# fastkey_-_v2.net
KiCad netlist of a schematic drawn in EAGLE
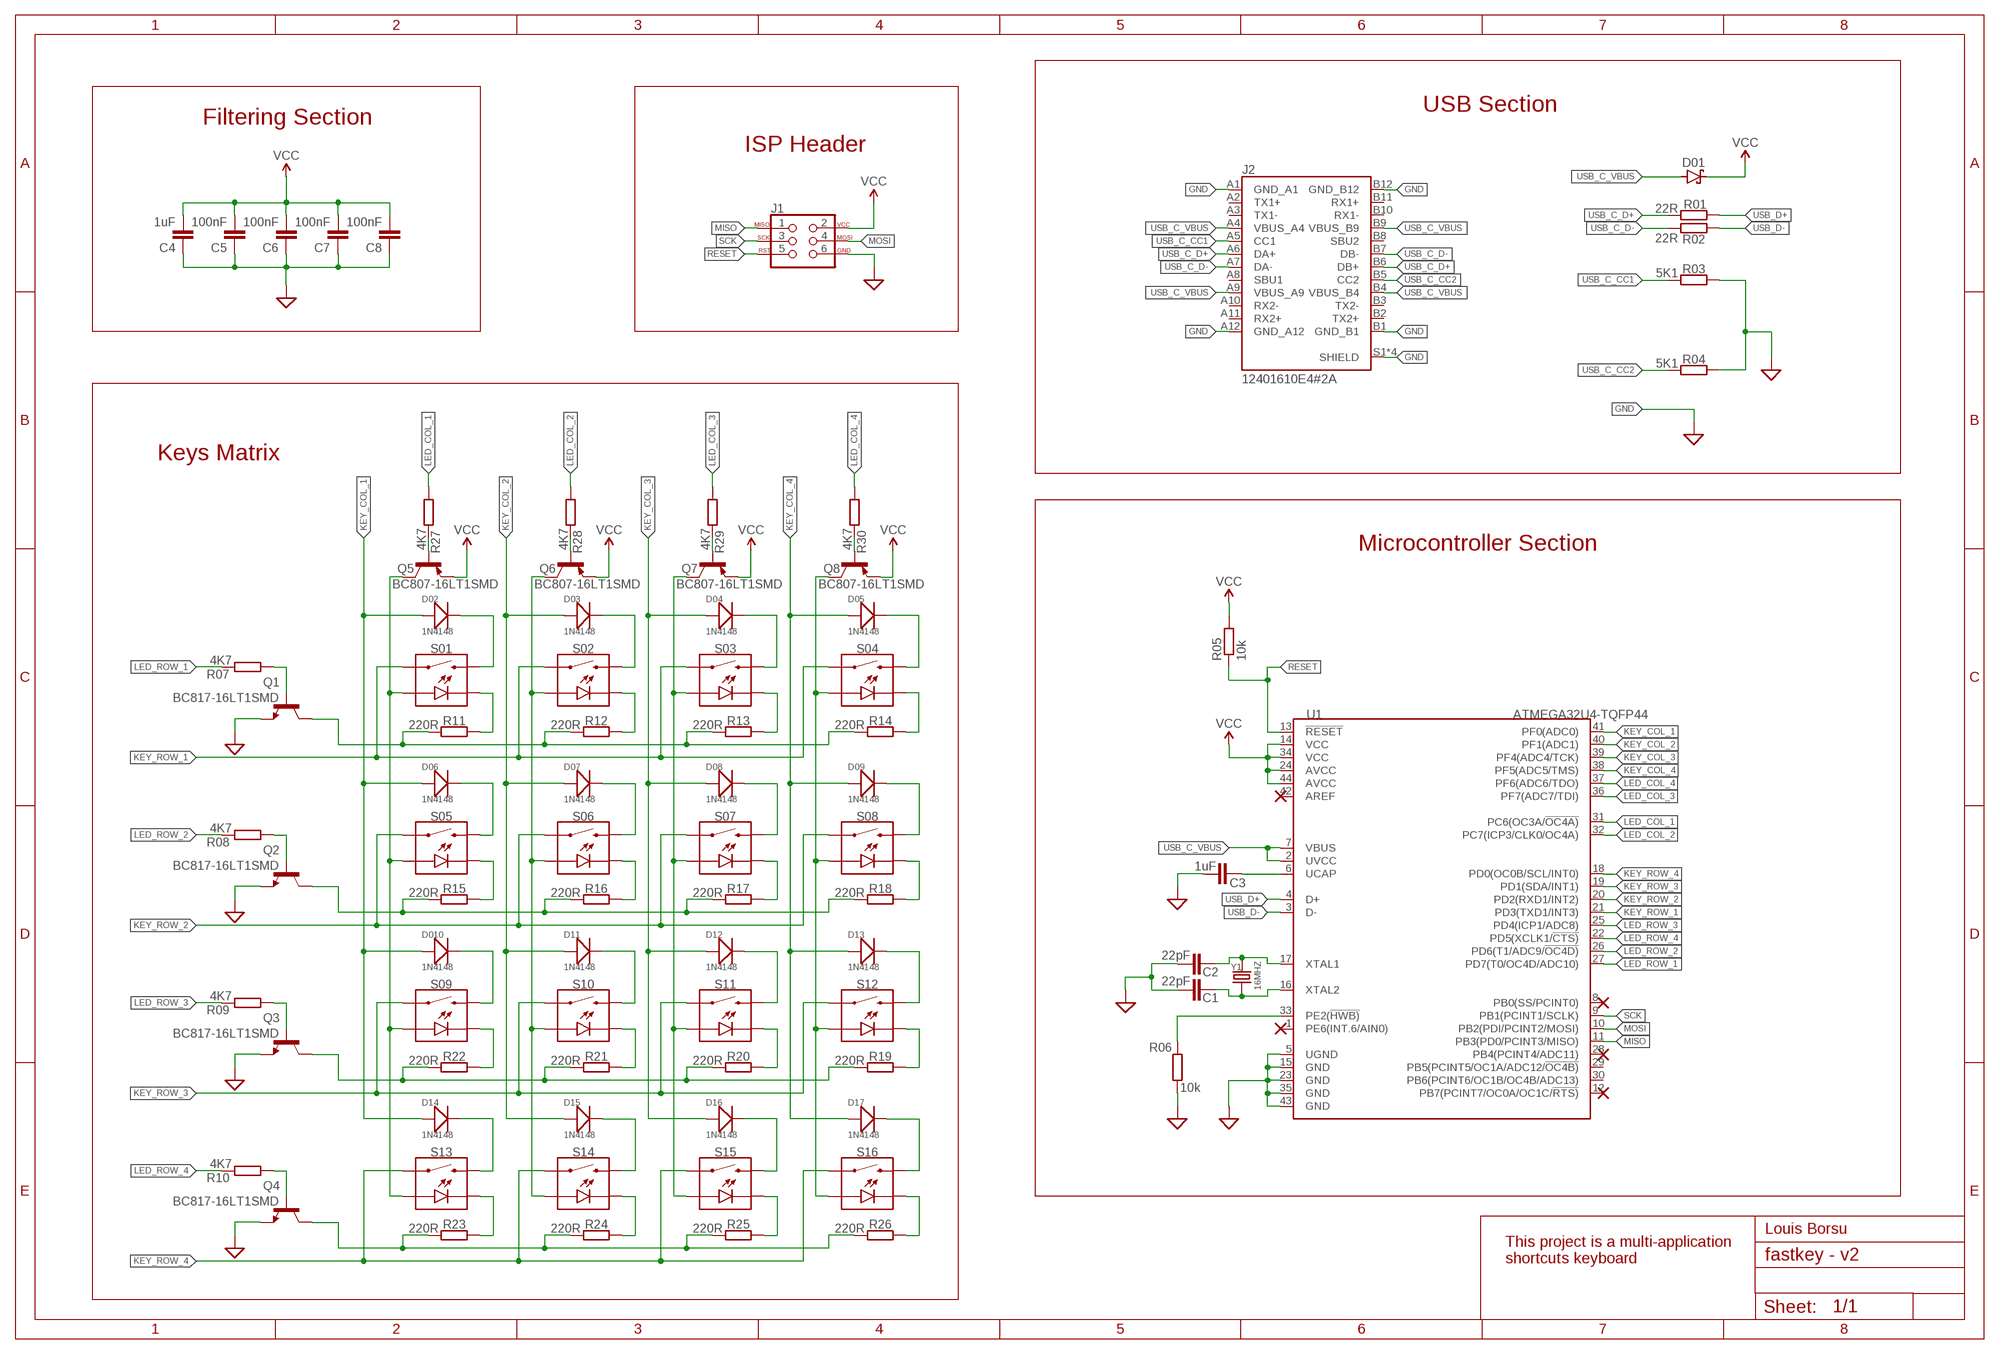
[diagram p0: schematic, sheet 1]

(export (version "E")
  (design (tool "Eeschema 10.0.6"))
  (components
    (comp (ref "C1")
      (value "22pF")
      (footprint "eagle-import:RESC0805_M")
      (fields (field (name "SPICEPREFIX") "C"))
      (libsource (lib "eagle-import") (part "CAPACITOR_0805_M"))
    )
    (comp (ref "C2")
      (value "22pF")
      (footprint "eagle-import:RESC0805_M")
      (fields (field (name "SPICEPREFIX") "C"))
      (libsource (lib "eagle-import") (part "CAPACITOR_0805_M"))
    )
    (comp (ref "C3")
      (value "1uF")
      (footprint "eagle-import:RESC0805_M")
      (fields (field (name "SPICEPREFIX") "C"))
      (libsource (lib "eagle-import") (part "CAPACITOR_0805_M"))
    )
    (comp (ref "C4")
      (value "1uF")
      (footprint "eagle-import:RESC0805_M")
      (fields (field (name "SPICEPREFIX") "C"))
      (libsource (lib "eagle-import") (part "CAPACITOR_0805_M"))
    )
    (comp (ref "C5")
      (value "100nF")
      (footprint "eagle-import:RESC0805_M")
      (fields (field (name "SPICEPREFIX") "C"))
      (libsource (lib "eagle-import") (part "CAPACITOR_0805_M"))
    )
    (comp (ref "C6")
      (value "100nF")
      (footprint "eagle-import:RESC0805_M")
      (libsource (lib "eagle-import") (part "CAPACITOR_0805_M"))
    )
    (comp (ref "C7")
      (value "100nF")
      (footprint "eagle-import:RESC0805_M")
      (fields (field (name "SPICEPREFIX") "C"))
      (libsource (lib "eagle-import") (part "CAPACITOR_0805_M"))
    )
    (comp (ref "C8")
      (value "100nF")
      (footprint "eagle-import:RESC0805_M")
      (fields (field (name "SPICEPREFIX") "C"))
      (libsource (lib "eagle-import") (part "CAPACITOR_0805_M"))
    )
    (comp (ref "D01")
      (value "SCHOTTKY-DIODESMD")
      (footprint "eagle-import:SMB")
      (libsource (lib "eagle-import") (part "SCHOTTKY-DIODESMD"))
    )
    (comp (ref "D02")
      (value "1N4148")
      (footprint "eagle-import:LL-34")
      (libsource (lib "eagle-import") (part "SMD-DIODE-SWITCH-1N4148(LL-34)"))
    )
    (comp (ref "D03")
      (value "1N4148")
      (footprint "eagle-import:LL-34")
      (libsource (lib "eagle-import") (part "SMD-DIODE-SWITCH-1N4148(LL-34)"))
    )
    (comp (ref "D04")
      (value "1N4148")
      (footprint "eagle-import:LL-34")
      (libsource (lib "eagle-import") (part "SMD-DIODE-SWITCH-1N4148(LL-34)"))
    )
    (comp (ref "D05")
      (value "1N4148")
      (footprint "eagle-import:LL-34")
      (libsource (lib "eagle-import") (part "SMD-DIODE-SWITCH-1N4148(LL-34)"))
    )
    (comp (ref "D06")
      (value "1N4148")
      (footprint "eagle-import:LL-34")
      (libsource (lib "eagle-import") (part "SMD-DIODE-SWITCH-1N4148(LL-34)"))
    )
    (comp (ref "D07")
      (value "1N4148")
      (footprint "eagle-import:LL-34")
      (libsource (lib "eagle-import") (part "SMD-DIODE-SWITCH-1N4148(LL-34)"))
    )
    (comp (ref "D08")
      (value "1N4148")
      (footprint "eagle-import:LL-34")
      (libsource (lib "eagle-import") (part "SMD-DIODE-SWITCH-1N4148(LL-34)"))
    )
    (comp (ref "D09")
      (value "1N4148")
      (footprint "eagle-import:LL-34")
      (libsource (lib "eagle-import") (part "SMD-DIODE-SWITCH-1N4148(LL-34)"))
    )
    (comp (ref "D010")
      (value "1N4148")
      (footprint "eagle-import:LL-34")
      (libsource (lib "eagle-import") (part "SMD-DIODE-SWITCH-1N4148(LL-34)"))
    )
    (comp (ref "D11")
      (value "1N4148")
      (footprint "eagle-import:LL-34")
      (libsource (lib "eagle-import") (part "SMD-DIODE-SWITCH-1N4148(LL-34)"))
    )
    (comp (ref "D12")
      (value "1N4148")
      (footprint "eagle-import:LL-34")
      (libsource (lib "eagle-import") (part "SMD-DIODE-SWITCH-1N4148(LL-34)"))
    )
    (comp (ref "D13")
      (value "1N4148")
      (footprint "eagle-import:LL-34")
      (libsource (lib "eagle-import") (part "SMD-DIODE-SWITCH-1N4148(LL-34)"))
    )
    (comp (ref "D14")
      (value "1N4148")
      (footprint "eagle-import:LL-34")
      (libsource (lib "eagle-import") (part "SMD-DIODE-SWITCH-1N4148(LL-34)"))
    )
    (comp (ref "D15")
      (value "1N4148")
      (footprint "eagle-import:LL-34")
      (libsource (lib "eagle-import") (part "SMD-DIODE-SWITCH-1N4148(LL-34)"))
    )
    (comp (ref "D16")
      (value "1N4148")
      (footprint "eagle-import:LL-34")
      (libsource (lib "eagle-import") (part "SMD-DIODE-SWITCH-1N4148(LL-34)"))
    )
    (comp (ref "D17")
      (value "1N4148")
      (footprint "eagle-import:LL-34")
      (libsource (lib "eagle-import") (part "SMD-DIODE-SWITCH-1N4148(LL-34)"))
    )
    (comp (ref "J1")
      (value "AVR_SPI_PROG_3X22X3_LOCK")
      (footprint "eagle-import:2X3_LOCK")
      (libsource (lib "eagle-import") (part "AVR_SPI_PROG_3X22X3_LOCK"))
    )
    (comp (ref "J2")
      (value "12401610E4#2A")
      (footprint "eagle-import:AMPHENOL_12401610E4#2A")
      (fields (field (name "DIGI-KEY_PART_NUMBER") "12401610E4#2ACT-ND") (field (name "MF") "Amphenol ICC"))
      (libsource (lib "eagle-import") (part "12401610E4#2A"))
    )
    (comp (ref "Q1")
      (value "BC817-16LT1SMD")
      (footprint "eagle-import:SOT23-BEC")
      (libsource (lib "eagle-import") (part "BC817SMD-16LT1"))
    )
    (comp (ref "Q2")
      (value "BC817-16LT1SMD")
      (footprint "eagle-import:SOT23-BEC")
      (libsource (lib "eagle-import") (part "BC817SMD-16LT1"))
    )
    (comp (ref "Q3")
      (value "BC817-16LT1SMD")
      (footprint "eagle-import:SOT23-BEC")
      (libsource (lib "eagle-import") (part "BC817SMD-16LT1"))
    )
    (comp (ref "Q4")
      (value "BC817-16LT1SMD")
      (footprint "eagle-import:SOT23-BEC")
      (libsource (lib "eagle-import") (part "BC817SMD-16LT1"))
    )
    (comp (ref "Q5")
      (value "BC807-16LT1SMD")
      (footprint "eagle-import:SOT23-BEC")
      (libsource (lib "eagle-import") (part "BC807SMD-16LT1"))
    )
    (comp (ref "Q6")
      (value "BC807-16LT1SMD")
      (footprint "eagle-import:SOT23-BEC")
      (libsource (lib "eagle-import") (part "BC807SMD-16LT1"))
    )
    (comp (ref "Q7")
      (value "BC807-16LT1SMD")
      (footprint "eagle-import:SOT23-BEC")
      (libsource (lib "eagle-import") (part "BC807SMD-16LT1"))
    )
    (comp (ref "Q8")
      (value "BC807-16LT1SMD")
      (footprint "eagle-import:SOT23-BEC")
      (libsource (lib "eagle-import") (part "BC807SMD-16LT1"))
    )
    (comp (ref "R01")
      (value "22R")
      (footprint "eagle-import:R0805")
      (libsource (lib "eagle-import") (part "R-EU_R0805"))
    )
    (comp (ref "R02")
      (value "22R")
      (footprint "eagle-import:R0805")
      (libsource (lib "eagle-import") (part "R-EU_R0805"))
    )
    (comp (ref "R03")
      (value "5K1")
      (footprint "eagle-import:R0805")
      (libsource (lib "eagle-import") (part "R-EU_R0805"))
    )
    (comp (ref "R04")
      (value "5K1")
      (footprint "eagle-import:R0805")
      (libsource (lib "eagle-import") (part "R-EU_R0805"))
    )
    (comp (ref "R05")
      (value "10k")
      (footprint "eagle-import:R0805")
      (libsource (lib "eagle-import") (part "R-EU_R0805"))
    )
    (comp (ref "R06")
      (value "10k")
      (footprint "eagle-import:R0805")
      (libsource (lib "eagle-import") (part "R-EU_R0805"))
    )
    (comp (ref "R07")
      (value "4K7")
      (footprint "eagle-import:R0805")
      (libsource (lib "eagle-import") (part "R-EU_R0805"))
    )
    (comp (ref "R08")
      (value "4K7")
      (footprint "eagle-import:R0805")
      (libsource (lib "eagle-import") (part "R-EU_R0805"))
    )
    (comp (ref "R09")
      (value "4K7")
      (footprint "eagle-import:R0805")
      (libsource (lib "eagle-import") (part "R-EU_R0805"))
    )
    (comp (ref "R10")
      (value "4K7")
      (footprint "eagle-import:R0805")
      (libsource (lib "eagle-import") (part "R-EU_R0805"))
    )
    (comp (ref "R11")
      (value "220R")
      (footprint "eagle-import:R0805")
      (libsource (lib "eagle-import") (part "R-EU_R0805"))
    )
    (comp (ref "R12")
      (value "220R")
      (footprint "eagle-import:R0805")
      (libsource (lib "eagle-import") (part "R-EU_R0805"))
    )
    (comp (ref "R13")
      (value "220R")
      (footprint "eagle-import:R0805")
      (libsource (lib "eagle-import") (part "R-EU_R0805"))
    )
    (comp (ref "R14")
      (value "220R")
      (footprint "eagle-import:R0805")
      (libsource (lib "eagle-import") (part "R-EU_R0805"))
    )
    (comp (ref "R15")
      (value "220R")
      (footprint "eagle-import:R0805")
      (libsource (lib "eagle-import") (part "R-EU_R0805"))
    )
    (comp (ref "R16")
      (value "220R")
      (footprint "eagle-import:R0805")
      (libsource (lib "eagle-import") (part "R-EU_R0805"))
    )
    (comp (ref "R17")
      (value "220R")
      (footprint "eagle-import:R0805")
      (libsource (lib "eagle-import") (part "R-EU_R0805"))
    )
    (comp (ref "R18")
      (value "220R")
      (footprint "eagle-import:R0805")
      (libsource (lib "eagle-import") (part "R-EU_R0805"))
    )
    (comp (ref "R19")
      (value "220R")
      (footprint "eagle-import:R0805")
      (libsource (lib "eagle-import") (part "R-EU_R0805"))
    )
    (comp (ref "R20")
      (value "220R")
      (footprint "eagle-import:R0805")
      (libsource (lib "eagle-import") (part "R-EU_R0805"))
    )
    (comp (ref "R21")
      (value "220R")
      (footprint "eagle-import:R0805")
      (libsource (lib "eagle-import") (part "R-EU_R0805"))
    )
    (comp (ref "R22")
      (value "220R")
      (footprint "eagle-import:R0805")
      (libsource (lib "eagle-import") (part "R-EU_R0805"))
    )
    (comp (ref "R23")
      (value "220R")
      (footprint "eagle-import:R0805")
      (libsource (lib "eagle-import") (part "R-EU_R0805"))
    )
    (comp (ref "R24")
      (value "220R")
      (footprint "eagle-import:R0805")
      (libsource (lib "eagle-import") (part "R-EU_R0805"))
    )
    (comp (ref "R25")
      (value "220R")
      (footprint "eagle-import:R0805")
      (libsource (lib "eagle-import") (part "R-EU_R0805"))
    )
    (comp (ref "R26")
      (value "220R")
      (footprint "eagle-import:R0805")
      (libsource (lib "eagle-import") (part "R-EU_R0805"))
    )
    (comp (ref "R27")
      (value "4K7")
      (footprint "eagle-import:R0805")
      (libsource (lib "eagle-import") (part "R-EU_R0805"))
    )
    (comp (ref "R28")
      (value "4K7")
      (footprint "eagle-import:R0805")
      (libsource (lib "eagle-import") (part "R-EU_R0805"))
    )
    (comp (ref "R29")
      (value "4K7")
      (footprint "eagle-import:R0805")
      (libsource (lib "eagle-import") (part "R-EU_R0805"))
    )
    (comp (ref "R30")
      (value "4K7")
      (footprint "eagle-import:R0805")
      (libsource (lib "eagle-import") (part "R-EU_R0805"))
    )
    (comp (ref "S01")
      (value "MOMENTARY-SWITCH-SPST-LED-PTH-CHERRY")
      (footprint "eagle-import:CHERRY-MX-LED")
      (libsource (lib "eagle-import") (part "MOMENTARY-SWITCH-SPST-LED-PTH-CHERRY"))
    )
    (comp (ref "S02")
      (value "MOMENTARY-SWITCH-SPST-LED-PTH-CHERRY")
      (footprint "eagle-import:CHERRY-MX-LED")
      (libsource (lib "eagle-import") (part "MOMENTARY-SWITCH-SPST-LED-PTH-CHERRY"))
    )
    (comp (ref "S03")
      (value "MOMENTARY-SWITCH-SPST-LED-PTH-CHERRY")
      (footprint "eagle-import:CHERRY-MX-LED")
      (libsource (lib "eagle-import") (part "MOMENTARY-SWITCH-SPST-LED-PTH-CHERRY"))
    )
    (comp (ref "S04")
      (value "MOMENTARY-SWITCH-SPST-LED-PTH-CHERRY")
      (footprint "eagle-import:CHERRY-MX-LED")
      (libsource (lib "eagle-import") (part "MOMENTARY-SWITCH-SPST-LED-PTH-CHERRY"))
    )
    (comp (ref "S05")
      (value "MOMENTARY-SWITCH-SPST-LED-PTH-CHERRY")
      (footprint "eagle-import:CHERRY-MX-LED")
      (libsource (lib "eagle-import") (part "MOMENTARY-SWITCH-SPST-LED-PTH-CHERRY"))
    )
    (comp (ref "S06")
      (value "MOMENTARY-SWITCH-SPST-LED-PTH-CHERRY")
      (footprint "eagle-import:CHERRY-MX-LED")
      (libsource (lib "eagle-import") (part "MOMENTARY-SWITCH-SPST-LED-PTH-CHERRY"))
    )
    (comp (ref "S07")
      (value "MOMENTARY-SWITCH-SPST-LED-PTH-CHERRY")
      (footprint "eagle-import:CHERRY-MX-LED")
      (libsource (lib "eagle-import") (part "MOMENTARY-SWITCH-SPST-LED-PTH-CHERRY"))
    )
    (comp (ref "S08")
      (value "MOMENTARY-SWITCH-SPST-LED-PTH-CHERRY")
      (footprint "eagle-import:CHERRY-MX-LED")
      (libsource (lib "eagle-import") (part "MOMENTARY-SWITCH-SPST-LED-PTH-CHERRY"))
    )
    (comp (ref "S09")
      (value "MOMENTARY-SWITCH-SPST-LED-PTH-CHERRY")
      (footprint "eagle-import:CHERRY-MX-LED")
      (libsource (lib "eagle-import") (part "MOMENTARY-SWITCH-SPST-LED-PTH-CHERRY"))
    )
    (comp (ref "S10")
      (value "MOMENTARY-SWITCH-SPST-LED-PTH-CHERRY")
      (footprint "eagle-import:CHERRY-MX-LED")
      (libsource (lib "eagle-import") (part "MOMENTARY-SWITCH-SPST-LED-PTH-CHERRY"))
    )
    (comp (ref "S11")
      (value "MOMENTARY-SWITCH-SPST-LED-PTH-CHERRY")
      (footprint "eagle-import:CHERRY-MX-LED")
      (libsource (lib "eagle-import") (part "MOMENTARY-SWITCH-SPST-LED-PTH-CHERRY"))
    )
    (comp (ref "S12")
      (value "MOMENTARY-SWITCH-SPST-LED-PTH-CHERRY")
      (footprint "eagle-import:CHERRY-MX-LED")
      (libsource (lib "eagle-import") (part "MOMENTARY-SWITCH-SPST-LED-PTH-CHERRY"))
    )
    (comp (ref "S13")
      (value "MOMENTARY-SWITCH-SPST-LED-PTH-CHERRY")
      (footprint "eagle-import:CHERRY-MX-LED")
      (libsource (lib "eagle-import") (part "MOMENTARY-SWITCH-SPST-LED-PTH-CHERRY"))
    )
    (comp (ref "S14")
      (value "MOMENTARY-SWITCH-SPST-LED-PTH-CHERRY")
      (footprint "eagle-import:CHERRY-MX-LED")
      (libsource (lib "eagle-import") (part "MOMENTARY-SWITCH-SPST-LED-PTH-CHERRY"))
    )
    (comp (ref "S15")
      (value "MOMENTARY-SWITCH-SPST-LED-PTH-CHERRY")
      (footprint "eagle-import:CHERRY-MX-LED")
      (libsource (lib "eagle-import") (part "MOMENTARY-SWITCH-SPST-LED-PTH-CHERRY"))
    )
    (comp (ref "S16")
      (value "MOMENTARY-SWITCH-SPST-LED-PTH-CHERRY")
      (footprint "eagle-import:CHERRY-MX-LED")
      (libsource (lib "eagle-import") (part "MOMENTARY-SWITCH-SPST-LED-PTH-CHERRY"))
    )
    (comp (ref "U1")
      (value "ATMEGA32U4-TQFP44")
      (footprint "eagle-import:TQFP44-0.8-9.6X9.6MM")
      (fields (field (name "MPN") "ATMEGA32U4"))
      (libsource (lib "eagle-import") (part "MCU-ATMEGA32U4-AU(TQFP44)"))
    )
    (comp (ref "Y1")
      (value "16MHZ")
      (footprint "eagle-import:X2-SMD-5.0X3.2X1.3MM")
      (fields (field (name "MPN") "X053201602002"))
      (libsource (lib "eagle-import") (part "SMD-CRYSTAL-16MHZ-8PF-20PPM-40R(2P-5.0X3.2MM)"))
    )
  )
  (nets
    (net (code "1") (name "GND") (class "Default")
      (node (ref "C1") (pin "1") (pinfunction "1_1") (pintype "passive"))
      (node (ref "C2") (pin "1") (pinfunction "1_1") (pintype "passive"))
      (node (ref "C3") (pin "1") (pinfunction "1_1") (pintype "passive"))
      (node (ref "C4") (pin "1") (pinfunction "1_1") (pintype "passive"))
      (node (ref "C5") (pin "1") (pinfunction "1_1") (pintype "passive"))
      (node (ref "C6") (pin "1") (pinfunction "1_1") (pintype "passive"))
      (node (ref "C7") (pin "1") (pinfunction "1_1") (pintype "passive"))
      (node (ref "C8") (pin "1") (pinfunction "1_1") (pintype "passive"))
      (node (ref "J1") (pin "6") (pinfunction "6_6") (pintype "passive"))
      (node (ref "J2") (pin "A1") (pinfunction "GND_A1_A1") (pintype "passive"))
      (node (ref "J2") (pin "A12") (pinfunction "GND_A12_A12") (pintype "passive"))
      (node (ref "J2") (pin "B1") (pinfunction "GND_B1_B1") (pintype "passive"))
      (node (ref "J2") (pin "B12") (pinfunction "GND_B12_B12") (pintype "passive"))
      (node (ref "J2") (pin "S1") (pinfunction "SHIELD_S1") (pintype "passive"))
      (node (ref "J2") (pin "S2") (pinfunction "SHIELD_S2") (pintype "passive"))
      (node (ref "J2") (pin "S3") (pinfunction "SHIELD_S3") (pintype "passive"))
      (node (ref "J2") (pin "S4") (pinfunction "SHIELD_S4") (pintype "passive"))
      (node (ref "Q1") (pin "E") (pinfunction "E_E") (pintype "passive"))
      (node (ref "Q2") (pin "E") (pinfunction "E_E") (pintype "passive"))
      (node (ref "Q3") (pin "E") (pinfunction "E_E") (pintype "passive"))
      (node (ref "Q4") (pin "E") (pinfunction "E_E") (pintype "passive"))
      (node (ref "R03") (pin "1") (pinfunction "1_1") (pintype "passive"))
      (node (ref "R04") (pin "1") (pinfunction "1_1") (pintype "passive"))
      (node (ref "R06") (pin "1") (pinfunction "1_1") (pintype "passive"))
      (node (ref "U1") (pin "15") (pinfunction "GND_15") (pintype "bidirectional"))
      (node (ref "U1") (pin "23") (pinfunction "GND_23") (pintype "bidirectional"))
      (node (ref "U1") (pin "35") (pinfunction "GND_35") (pintype "bidirectional"))
      (node (ref "U1") (pin "43") (pinfunction "GND_43") (pintype "bidirectional"))
      (node (ref "U1") (pin "5") (pinfunction "UGND_5") (pintype "bidirectional"))
    )
    (net (code "2") (name "KEY_COL_1") (class "Default")
      (node (ref "D010") (pin "A") (pinfunction "+_A") (pintype "passive"))
      (node (ref "D02") (pin "A") (pinfunction "+_A") (pintype "passive"))
      (node (ref "D06") (pin "A") (pinfunction "+_A") (pintype "passive"))
      (node (ref "D14") (pin "A") (pinfunction "+_A") (pintype "passive"))
      (node (ref "U1") (pin "41") (pinfunction "PF0(ADC0)_41") (pintype "bidirectional"))
    )
    (net (code "3") (name "KEY_COL_2") (class "Default")
      (node (ref "D03") (pin "A") (pinfunction "+_A") (pintype "passive"))
      (node (ref "D07") (pin "A") (pinfunction "+_A") (pintype "passive"))
      (node (ref "D11") (pin "A") (pinfunction "+_A") (pintype "passive"))
      (node (ref "D15") (pin "A") (pinfunction "+_A") (pintype "passive"))
      (node (ref "U1") (pin "40") (pinfunction "PF1(ADC1)_40") (pintype "bidirectional"))
    )
    (net (code "4") (name "KEY_COL_3") (class "Default")
      (node (ref "D04") (pin "A") (pinfunction "+_A") (pintype "passive"))
      (node (ref "D08") (pin "A") (pinfunction "+_A") (pintype "passive"))
      (node (ref "D12") (pin "A") (pinfunction "+_A") (pintype "passive"))
      (node (ref "D16") (pin "A") (pinfunction "+_A") (pintype "passive"))
      (node (ref "U1") (pin "39") (pinfunction "PF4(ADC4/TCK)_39") (pintype "bidirectional"))
    )
    (net (code "5") (name "KEY_COL_4") (class "Default")
      (node (ref "D05") (pin "A") (pinfunction "+_A") (pintype "passive"))
      (node (ref "D09") (pin "A") (pinfunction "+_A") (pintype "passive"))
      (node (ref "D13") (pin "A") (pinfunction "+_A") (pintype "passive"))
      (node (ref "D17") (pin "A") (pinfunction "+_A") (pintype "passive"))
      (node (ref "U1") (pin "38") (pinfunction "PF5(ADC5/TMS)_38") (pintype "bidirectional"))
    )
    (net (code "6") (name "KEY_ROW_1") (class "Default")
      (node (ref "S01") (pin "S1") (pinfunction "1_S1") (pintype "passive"))
      (node (ref "S02") (pin "S1") (pinfunction "1_S1") (pintype "passive"))
      (node (ref "S03") (pin "S1") (pinfunction "1_S1") (pintype "passive"))
      (node (ref "S04") (pin "S1") (pinfunction "1_S1") (pintype "passive"))
      (node (ref "U1") (pin "21") (pinfunction "PD3(TXD1/INT3)_21") (pintype "bidirectional"))
    )
    (net (code "7") (name "KEY_ROW_2") (class "Default")
      (node (ref "S05") (pin "S1") (pinfunction "1_S1") (pintype "passive"))
      (node (ref "S06") (pin "S1") (pinfunction "1_S1") (pintype "passive"))
      (node (ref "S07") (pin "S1") (pinfunction "1_S1") (pintype "passive"))
      (node (ref "S08") (pin "S1") (pinfunction "1_S1") (pintype "passive"))
      (node (ref "U1") (pin "20") (pinfunction "PD2(RXD1/INT2)_20") (pintype "bidirectional"))
    )
    (net (code "8") (name "KEY_ROW_3") (class "Default")
      (node (ref "S09") (pin "S1") (pinfunction "1_S1") (pintype "passive"))
      (node (ref "S10") (pin "S1") (pinfunction "1_S1") (pintype "passive"))
      (node (ref "S11") (pin "S1") (pinfunction "1_S1") (pintype "passive"))
      (node (ref "S12") (pin "S1") (pinfunction "1_S1") (pintype "passive"))
      (node (ref "U1") (pin "19") (pinfunction "PD1(SDA/INT1)_19") (pintype "bidirectional"))
    )
    (net (code "9") (name "KEY_ROW_4") (class "Default")
      (node (ref "S13") (pin "S1") (pinfunction "1_S1") (pintype "passive"))
      (node (ref "S14") (pin "S1") (pinfunction "1_S1") (pintype "passive"))
      (node (ref "S15") (pin "S1") (pinfunction "1_S1") (pintype "passive"))
      (node (ref "S16") (pin "S1") (pinfunction "1_S1") (pintype "passive"))
      (node (ref "U1") (pin "18") (pinfunction "PD0(OC0B/SCL/INT0)_18") (pintype "bidirectional"))
    )
    (net (code "10") (name "LED_COL_1") (class "Default")
      (node (ref "R27") (pin "1") (pinfunction "1_1") (pintype "passive"))
      (node (ref "U1") (pin "31") (pinfunction "PC6(OC3A/~{OC4A})_31") (pintype "bidirectional"))
    )
    (net (code "11") (name "LED_COL_2") (class "Default")
      (node (ref "R28") (pin "1") (pinfunction "1_1") (pintype "passive"))
      (node (ref "U1") (pin "32") (pinfunction "PC7(ICP3/CLK0/OC4A)_32") (pintype "bidirectional"))
    )
    (net (code "12") (name "LED_COL_3") (class "Default")
      (node (ref "R29") (pin "1") (pinfunction "1_1") (pintype "passive"))
      (node (ref "U1") (pin "36") (pinfunction "PF7(ADC7/TDI)_36") (pintype "bidirectional"))
    )
    (net (code "13") (name "LED_COL_4") (class "Default")
      (node (ref "R30") (pin "1") (pinfunction "1_1") (pintype "passive"))
      (node (ref "U1") (pin "37") (pinfunction "PF6(ADC6/TDO)_37") (pintype "bidirectional"))
    )
    (net (code "14") (name "LED_ROW_1") (class "Default")
      (node (ref "R07") (pin "2") (pinfunction "2_2") (pintype "passive"))
      (node (ref "U1") (pin "27") (pinfunction "PD7(T0/OC4D/ADC10)_27") (pintype "bidirectional"))
    )
    (net (code "15") (name "LED_ROW_2") (class "Default")
      (node (ref "R08") (pin "2") (pinfunction "2_2") (pintype "passive"))
      (node (ref "U1") (pin "26") (pinfunction "PD6(T1/ADC9/~{OC4D})_26") (pintype "bidirectional"))
    )
    (net (code "16") (name "LED_ROW_3") (class "Default")
      (node (ref "R09") (pin "2") (pinfunction "2_2") (pintype "passive"))
      (node (ref "U1") (pin "25") (pinfunction "PD4(ICP1/ADC8)_25") (pintype "bidirectional"))
    )
    (net (code "17") (name "LED_ROW_4") (class "Default")
      (node (ref "R10") (pin "2") (pinfunction "2_2") (pintype "passive"))
      (node (ref "U1") (pin "22") (pinfunction "PD5(XCLK1/~{CTS})_22") (pintype "bidirectional"))
    )
    (net (code "18") (name "MISO") (class "Default")
      (node (ref "J1") (pin "1") (pinfunction "1_1") (pintype "passive"))
      (node (ref "U1") (pin "11") (pinfunction "PB3(PD0/PCINT3/MISO)_11") (pintype "bidirectional"))
    )
    (net (code "19") (name "MOSI") (class "Default")
      (node (ref "J1") (pin "4") (pinfunction "4_4") (pintype "passive"))
      (node (ref "U1") (pin "10") (pinfunction "PB2(PDI/PCINT2/MOSI)_10") (pintype "bidirectional"))
    )
    (net (code "20") (name "Net-(D02--)") (class "Default")
      (node (ref "D02") (pin "C") (pinfunction "-_C") (pintype "passive"))
      (node (ref "S01") (pin "S2") (pinfunction "2_S2") (pintype "passive"))
    )
    (net (code "21") (name "Net-(D03--)") (class "Default")
      (node (ref "D03") (pin "C") (pinfunction "-_C") (pintype "passive"))
      (node (ref "S02") (pin "S2") (pinfunction "2_S2") (pintype "passive"))
    )
    (net (code "22") (name "Net-(D04--)") (class "Default")
      (node (ref "D04") (pin "C") (pinfunction "-_C") (pintype "passive"))
      (node (ref "S03") (pin "S2") (pinfunction "2_S2") (pintype "passive"))
    )
    (net (code "23") (name "Net-(D05--)") (class "Default")
      (node (ref "D05") (pin "C") (pinfunction "-_C") (pintype "passive"))
      (node (ref "S04") (pin "S2") (pinfunction "2_S2") (pintype "passive"))
    )
    (net (code "24") (name "Net-(D06--)") (class "Default")
      (node (ref "D06") (pin "C") (pinfunction "-_C") (pintype "passive"))
      (node (ref "S05") (pin "S2") (pinfunction "2_S2") (pintype "passive"))
    )
    (net (code "25") (name "Net-(D07--)") (class "Default")
      (node (ref "D07") (pin "C") (pinfunction "-_C") (pintype "passive"))
      (node (ref "S06") (pin "S2") (pinfunction "2_S2") (pintype "passive"))
    )
    (net (code "26") (name "Net-(D08--)") (class "Default")
      (node (ref "D08") (pin "C") (pinfunction "-_C") (pintype "passive"))
      (node (ref "S07") (pin "S2") (pinfunction "2_S2") (pintype "passive"))
    )
    (net (code "27") (name "Net-(D09--)") (class "Default")
      (node (ref "D09") (pin "C") (pinfunction "-_C") (pintype "passive"))
      (node (ref "S08") (pin "S2") (pinfunction "2_S2") (pintype "passive"))
    )
    (net (code "28") (name "Net-(D010--)") (class "Default")
      (node (ref "D010") (pin "C") (pinfunction "-_C") (pintype "passive"))
      (node (ref "S09") (pin "S2") (pinfunction "2_S2") (pintype "passive"))
    )
    (net (code "29") (name "Net-(D11--)") (class "Default")
      (node (ref "D11") (pin "C") (pinfunction "-_C") (pintype "passive"))
      (node (ref "S10") (pin "S2") (pinfunction "2_S2") (pintype "passive"))
    )
    (net (code "30") (name "Net-(D12--)") (class "Default")
      (node (ref "D12") (pin "C") (pinfunction "-_C") (pintype "passive"))
      (node (ref "S11") (pin "S2") (pinfunction "2_S2") (pintype "passive"))
    )
    (net (code "31") (name "Net-(D13--)") (class "Default")
      (node (ref "D13") (pin "C") (pinfunction "-_C") (pintype "passive"))
      (node (ref "S12") (pin "S2") (pinfunction "2_S2") (pintype "passive"))
    )
    (net (code "32") (name "Net-(D14--)") (class "Default")
      (node (ref "D14") (pin "C") (pinfunction "-_C") (pintype "passive"))
      (node (ref "S13") (pin "S2") (pinfunction "2_S2") (pintype "passive"))
    )
    (net (code "33") (name "Net-(D15--)") (class "Default")
      (node (ref "D15") (pin "C") (pinfunction "-_C") (pintype "passive"))
      (node (ref "S14") (pin "S2") (pinfunction "2_S2") (pintype "passive"))
    )
    (net (code "34") (name "Net-(D16--)") (class "Default")
      (node (ref "D16") (pin "C") (pinfunction "-_C") (pintype "passive"))
      (node (ref "S15") (pin "S2") (pinfunction "2_S2") (pintype "passive"))
    )
    (net (code "35") (name "Net-(D17--)") (class "Default")
      (node (ref "D17") (pin "C") (pinfunction "-_C") (pintype "passive"))
      (node (ref "S16") (pin "S2") (pinfunction "2_S2") (pintype "passive"))
    )
    (net (code "36") (name "Net-(Q1-PadB)") (class "Default")
      (node (ref "Q1") (pin "B") (pinfunction "B_B") (pintype "passive"))
      (node (ref "R07") (pin "1") (pinfunction "1_1") (pintype "passive"))
    )
    (net (code "37") (name "Net-(Q1-PadC)") (class "Default")
      (node (ref "Q1") (pin "C") (pinfunction "C_C") (pintype "passive"))
      (node (ref "R11") (pin "2") (pinfunction "2_2") (pintype "passive"))
      (node (ref "R12") (pin "2") (pinfunction "2_2") (pintype "passive"))
      (node (ref "R13") (pin "2") (pinfunction "2_2") (pintype "passive"))
      (node (ref "R14") (pin "2") (pinfunction "2_2") (pintype "passive"))
    )
    (net (code "38") (name "Net-(Q2-PadB)") (class "Default")
      (node (ref "Q2") (pin "B") (pinfunction "B_B") (pintype "passive"))
      (node (ref "R08") (pin "1") (pinfunction "1_1") (pintype "passive"))
    )
    (net (code "39") (name "Net-(Q2-PadC)") (class "Default")
      (node (ref "Q2") (pin "C") (pinfunction "C_C") (pintype "passive"))
      (node (ref "R15") (pin "2") (pinfunction "2_2") (pintype "passive"))
      (node (ref "R16") (pin "2") (pinfunction "2_2") (pintype "passive"))
      (node (ref "R17") (pin "2") (pinfunction "2_2") (pintype "passive"))
      (node (ref "R18") (pin "2") (pinfunction "2_2") (pintype "passive"))
    )
    (net (code "40") (name "Net-(Q3-PadB)") (class "Default")
      (node (ref "Q3") (pin "B") (pinfunction "B_B") (pintype "passive"))
      (node (ref "R09") (pin "1") (pinfunction "1_1") (pintype "passive"))
    )
    (net (code "41") (name "Net-(Q3-PadC)") (class "Default")
      (node (ref "Q3") (pin "C") (pinfunction "C_C") (pintype "passive"))
      (node (ref "R19") (pin "2") (pinfunction "2_2") (pintype "passive"))
      (node (ref "R20") (pin "2") (pinfunction "2_2") (pintype "passive"))
      (node (ref "R21") (pin "2") (pinfunction "2_2") (pintype "passive"))
      (node (ref "R22") (pin "2") (pinfunction "2_2") (pintype "passive"))
    )
    (net (code "42") (name "Net-(Q4-PadB)") (class "Default")
      (node (ref "Q4") (pin "B") (pinfunction "B_B") (pintype "passive"))
      (node (ref "R10") (pin "1") (pinfunction "1_1") (pintype "passive"))
    )
    (net (code "43") (name "Net-(Q4-PadC)") (class "Default")
      (node (ref "Q4") (pin "C") (pinfunction "C_C") (pintype "passive"))
      (node (ref "R23") (pin "2") (pinfunction "2_2") (pintype "passive"))
      (node (ref "R24") (pin "2") (pinfunction "2_2") (pintype "passive"))
      (node (ref "R25") (pin "2") (pinfunction "2_2") (pintype "passive"))
      (node (ref "R26") (pin "2") (pinfunction "2_2") (pintype "passive"))
    )
    (net (code "44") (name "Net-(Q5-PadB)") (class "Default")
      (node (ref "Q5") (pin "B") (pinfunction "B_B") (pintype "passive"))
      (node (ref "R27") (pin "2") (pinfunction "2_2") (pintype "passive"))
    )
    (net (code "45") (name "Net-(Q5-PadC)") (class "Default")
      (node (ref "Q5") (pin "C") (pinfunction "C_C") (pintype "passive"))
      (node (ref "S01") (pin "A") (pinfunction "A_A") (pintype "passive"))
      (node (ref "S05") (pin "A") (pinfunction "A_A") (pintype "passive"))
      (node (ref "S09") (pin "A") (pinfunction "A_A") (pintype "passive"))
      (node (ref "S13") (pin "A") (pinfunction "A_A") (pintype "passive"))
    )
    (net (code "46") (name "Net-(Q6-PadB)") (class "Default")
      (node (ref "Q6") (pin "B") (pinfunction "B_B") (pintype "passive"))
      (node (ref "R28") (pin "2") (pinfunction "2_2") (pintype "passive"))
    )
    (net (code "47") (name "Net-(Q6-PadC)") (class "Default")
      (node (ref "Q6") (pin "C") (pinfunction "C_C") (pintype "passive"))
      (node (ref "S02") (pin "A") (pinfunction "A_A") (pintype "passive"))
      (node (ref "S06") (pin "A") (pinfunction "A_A") (pintype "passive"))
      (node (ref "S10") (pin "A") (pinfunction "A_A") (pintype "passive"))
      (node (ref "S14") (pin "A") (pinfunction "A_A") (pintype "passive"))
    )
    (net (code "48") (name "Net-(Q7-PadB)") (class "Default")
      (node (ref "Q7") (pin "B") (pinfunction "B_B") (pintype "passive"))
      (node (ref "R29") (pin "2") (pinfunction "2_2") (pintype "passive"))
    )
    (net (code "49") (name "Net-(Q7-PadC)") (class "Default")
      (node (ref "Q7") (pin "C") (pinfunction "C_C") (pintype "passive"))
      (node (ref "S03") (pin "A") (pinfunction "A_A") (pintype "passive"))
      (node (ref "S07") (pin "A") (pinfunction "A_A") (pintype "passive"))
      (node (ref "S11") (pin "A") (pinfunction "A_A") (pintype "passive"))
      (node (ref "S15") (pin "A") (pinfunction "A_A") (pintype "passive"))
    )
    (net (code "50") (name "Net-(Q8-PadB)") (class "Default")
      (node (ref "Q8") (pin "B") (pinfunction "B_B") (pintype "passive"))
      (node (ref "R30") (pin "2") (pinfunction "2_2") (pintype "passive"))
    )
    (net (code "51") (name "Net-(Q8-PadC)") (class "Default")
      (node (ref "Q8") (pin "C") (pinfunction "C_C") (pintype "passive"))
      (node (ref "S04") (pin "A") (pinfunction "A_A") (pintype "passive"))
      (node (ref "S08") (pin "A") (pinfunction "A_A") (pintype "passive"))
      (node (ref "S12") (pin "A") (pinfunction "A_A") (pintype "passive"))
      (node (ref "S16") (pin "A") (pinfunction "A_A") (pintype "passive"))
    )
    (net (code "52") (name "Net-(S01-C)") (class "Default")
      (node (ref "R11") (pin "1") (pinfunction "1_1") (pintype "passive"))
      (node (ref "S01") (pin "K") (pinfunction "C_K") (pintype "passive"))
    )
    (net (code "53") (name "Net-(S02-C)") (class "Default")
      (node (ref "R12") (pin "1") (pinfunction "1_1") (pintype "passive"))
      (node (ref "S02") (pin "K") (pinfunction "C_K") (pintype "passive"))
    )
    (net (code "54") (name "Net-(S03-C)") (class "Default")
      (node (ref "R13") (pin "1") (pinfunction "1_1") (pintype "passive"))
      (node (ref "S03") (pin "K") (pinfunction "C_K") (pintype "passive"))
    )
    (net (code "55") (name "Net-(S04-C)") (class "Default")
      (node (ref "R14") (pin "1") (pinfunction "1_1") (pintype "passive"))
      (node (ref "S04") (pin "K") (pinfunction "C_K") (pintype "passive"))
    )
    (net (code "56") (name "Net-(S05-C)") (class "Default")
      (node (ref "R15") (pin "1") (pinfunction "1_1") (pintype "passive"))
      (node (ref "S05") (pin "K") (pinfunction "C_K") (pintype "passive"))
    )
    (net (code "57") (name "Net-(S06-C)") (class "Default")
      (node (ref "R16") (pin "1") (pinfunction "1_1") (pintype "passive"))
      (node (ref "S06") (pin "K") (pinfunction "C_K") (pintype "passive"))
    )
    (net (code "58") (name "Net-(S07-C)") (class "Default")
      (node (ref "R17") (pin "1") (pinfunction "1_1") (pintype "passive"))
      (node (ref "S07") (pin "K") (pinfunction "C_K") (pintype "passive"))
    )
    (net (code "59") (name "Net-(S08-C)") (class "Default")
      (node (ref "R18") (pin "1") (pinfunction "1_1") (pintype "passive"))
      (node (ref "S08") (pin "K") (pinfunction "C_K") (pintype "passive"))
    )
    (net (code "60") (name "Net-(S09-C)") (class "Default")
      (node (ref "R22") (pin "1") (pinfunction "1_1") (pintype "passive"))
      (node (ref "S09") (pin "K") (pinfunction "C_K") (pintype "passive"))
    )
    (net (code "61") (name "Net-(S10-C)") (class "Default")
      (node (ref "R21") (pin "1") (pinfunction "1_1") (pintype "passive"))
      (node (ref "S10") (pin "K") (pinfunction "C_K") (pintype "passive"))
    )
    (net (code "62") (name "Net-(S11-C)") (class "Default")
      (node (ref "R20") (pin "1") (pinfunction "1_1") (pintype "passive"))
      (node (ref "S11") (pin "K") (pinfunction "C_K") (pintype "passive"))
    )
    (net (code "63") (name "Net-(S12-C)") (class "Default")
      (node (ref "R19") (pin "1") (pinfunction "1_1") (pintype "passive"))
      (node (ref "S12") (pin "K") (pinfunction "C_K") (pintype "passive"))
    )
    (net (code "64") (name "Net-(S13-C)") (class "Default")
      (node (ref "R23") (pin "1") (pinfunction "1_1") (pintype "passive"))
      (node (ref "S13") (pin "K") (pinfunction "C_K") (pintype "passive"))
    )
    (net (code "65") (name "Net-(S14-C)") (class "Default")
      (node (ref "R24") (pin "1") (pinfunction "1_1") (pintype "passive"))
      (node (ref "S14") (pin "K") (pinfunction "C_K") (pintype "passive"))
    )
    (net (code "66") (name "Net-(S15-C)") (class "Default")
      (node (ref "R25") (pin "1") (pinfunction "1_1") (pintype "passive"))
      (node (ref "S15") (pin "K") (pinfunction "C_K") (pintype "passive"))
    )
    (net (code "67") (name "Net-(S16-C)") (class "Default")
      (node (ref "R26") (pin "1") (pinfunction "1_1") (pintype "passive"))
      (node (ref "S16") (pin "K") (pinfunction "C_K") (pintype "passive"))
    )
    (net (code "68") (name "Net-(U1-PE2(~{HWB}))") (class "Default")
      (node (ref "R06") (pin "2") (pinfunction "2_2") (pintype "passive"))
      (node (ref "U1") (pin "33") (pinfunction "PE2(~{HWB})_33") (pintype "bidirectional"))
    )
    (net (code "69") (name "Net-(U1-UCAP)") (class "Default")
      (node (ref "C3") (pin "2") (pinfunction "2_2") (pintype "passive"))
      (node (ref "U1") (pin "6") (pinfunction "UCAP_6") (pintype "bidirectional"))
    )
    (net (code "70") (name "Net-(U1-XTAL1)") (class "Default")
      (node (ref "C2") (pin "2") (pinfunction "2_2") (pintype "passive"))
      (node (ref "U1") (pin "17") (pinfunction "XTAL1_17") (pintype "bidirectional"))
      (node (ref "Y1") (pin "2") (pinfunction "2_2") (pintype "passive"))
    )
    (net (code "71") (name "Net-(U1-XTAL2)") (class "Default")
      (node (ref "C1") (pin "2") (pinfunction "2_2") (pintype "passive"))
      (node (ref "U1") (pin "16") (pinfunction "XTAL2_16") (pintype "bidirectional"))
      (node (ref "Y1") (pin "1") (pinfunction "1_1") (pintype "passive"))
    )
    (net (code "72") (name "RESET") (class "Default")
      (node (ref "J1") (pin "5") (pinfunction "5_5") (pintype "passive"))
      (node (ref "R05") (pin "1") (pinfunction "1_1") (pintype "passive"))
      (node (ref "U1") (pin "13") (pinfunction "~{RESET}_13") (pintype "bidirectional"))
    )
    (net (code "73") (name "SCK") (class "Default")
      (node (ref "J1") (pin "3") (pinfunction "3_3") (pintype "passive"))
      (node (ref "U1") (pin "9") (pinfunction "PB1(PCINT1/SCLK)_9") (pintype "bidirectional"))
    )
    (net (code "74") (name "USB_C_CC1") (class "Default")
      (node (ref "J2") (pin "A5") (pinfunction "CC1_A5") (pintype "passive"))
      (node (ref "R03") (pin "2") (pinfunction "2_2") (pintype "passive"))
    )
    (net (code "75") (name "USB_C_CC2") (class "Default")
      (node (ref "J2") (pin "B5") (pinfunction "CC2_B5") (pintype "passive"))
      (node (ref "R04") (pin "2") (pinfunction "2_2") (pintype "passive"))
    )
    (net (code "76") (name "USB_C_D+") (class "Default")
      (node (ref "J2") (pin "A6") (pinfunction "DA+_A6") (pintype "passive"))
      (node (ref "J2") (pin "B6") (pinfunction "DB+_B6") (pintype "passive"))
      (node (ref "R01") (pin "2") (pinfunction "2_2") (pintype "passive"))
    )
    (net (code "77") (name "USB_C_D-") (class "Default")
      (node (ref "J2") (pin "A7") (pinfunction "DA-_A7") (pintype "passive"))
      (node (ref "J2") (pin "B7") (pinfunction "DB-_B7") (pintype "passive"))
      (node (ref "R02") (pin "2") (pinfunction "2_2") (pintype "passive"))
    )
    (net (code "78") (name "USB_C_VBUS") (class "Default")
      (node (ref "D01") (pin "A") (pinfunction "A_A") (pintype "passive"))
      (node (ref "J2") (pin "A4") (pinfunction "VBUS_A4_A4") (pintype "passive"))
      (node (ref "J2") (pin "A9") (pinfunction "VBUS_A9_A9") (pintype "passive"))
      (node (ref "J2") (pin "B4") (pinfunction "VBUS_B4_B4") (pintype "passive"))
      (node (ref "J2") (pin "B9") (pinfunction "VBUS_B9_B9") (pintype "passive"))
      (node (ref "U1") (pin "2") (pinfunction "UVCC_2") (pintype "bidirectional"))
      (node (ref "U1") (pin "7") (pinfunction "VBUS_7") (pintype "bidirectional"))
    )
    (net (code "79") (name "USB_D+") (class "Default")
      (node (ref "R01") (pin "1") (pinfunction "1_1") (pintype "passive"))
      (node (ref "U1") (pin "4") (pinfunction "D+_4") (pintype "bidirectional"))
    )
    (net (code "80") (name "USB_D-") (class "Default")
      (node (ref "R02") (pin "1") (pinfunction "1_1") (pintype "passive"))
      (node (ref "U1") (pin "3") (pinfunction "D-_3") (pintype "bidirectional"))
    )
    (net (code "81") (name "VCC") (class "Default")
      (node (ref "C4") (pin "2") (pinfunction "2_2") (pintype "passive"))
      (node (ref "C5") (pin "2") (pinfunction "2_2") (pintype "passive"))
      (node (ref "C6") (pin "2") (pinfunction "2_2") (pintype "passive"))
      (node (ref "C7") (pin "2") (pinfunction "2_2") (pintype "passive"))
      (node (ref "C8") (pin "2") (pinfunction "2_2") (pintype "passive"))
      (node (ref "D01") (pin "C") (pinfunction "C_C") (pintype "passive"))
      (node (ref "J1") (pin "2") (pinfunction "2_2") (pintype "passive"))
      (node (ref "Q5") (pin "E") (pinfunction "E_E") (pintype "passive"))
      (node (ref "Q6") (pin "E") (pinfunction "E_E") (pintype "passive"))
      (node (ref "Q7") (pin "E") (pinfunction "E_E") (pintype "passive"))
      (node (ref "Q8") (pin "E") (pinfunction "E_E") (pintype "passive"))
      (node (ref "R05") (pin "2") (pinfunction "2_2") (pintype "passive"))
      (node (ref "U1") (pin "14") (pinfunction "VCC_14") (pintype "bidirectional"))
      (node (ref "U1") (pin "24") (pinfunction "AVCC_24") (pintype "bidirectional"))
      (node (ref "U1") (pin "34") (pinfunction "VCC_34") (pintype "bidirectional"))
      (node (ref "U1") (pin "44") (pinfunction "AVCC_44") (pintype "bidirectional"))
    )
    (net (code "82") (name "unconnected-(J2-RX1+-PadB11)") (class "Default")
      (node (ref "J2") (pin "B11") (pinfunction "RX1+_B11") (pintype "passive"))
    )
    (net (code "83") (name "unconnected-(J2-RX1--PadB10)") (class "Default")
      (node (ref "J2") (pin "B10") (pinfunction "RX1-_B10") (pintype "passive"))
    )
    (net (code "84") (name "unconnected-(J2-RX2+-PadA11)") (class "Default")
      (node (ref "J2") (pin "A11") (pinfunction "RX2+_A11") (pintype "passive"))
    )
    (net (code "85") (name "unconnected-(J2-RX2--PadA10)") (class "Default")
      (node (ref "J2") (pin "A10") (pinfunction "RX2-_A10") (pintype "passive"))
    )
    (net (code "86") (name "unconnected-(J2-SBU1-PadA8)") (class "Default")
      (node (ref "J2") (pin "A8") (pinfunction "SBU1_A8") (pintype "passive"))
    )
    (net (code "87") (name "unconnected-(J2-SBU2-PadB8)") (class "Default")
      (node (ref "J2") (pin "B8") (pinfunction "SBU2_B8") (pintype "passive"))
    )
    (net (code "88") (name "unconnected-(J2-TX1+-PadA2)") (class "Default")
      (node (ref "J2") (pin "A2") (pinfunction "TX1+_A2") (pintype "passive"))
    )
    (net (code "89") (name "unconnected-(J2-TX1--PadA3)") (class "Default")
      (node (ref "J2") (pin "A3") (pinfunction "TX1-_A3") (pintype "passive"))
    )
    (net (code "90") (name "unconnected-(J2-TX2+-PadB2)") (class "Default")
      (node (ref "J2") (pin "B2") (pinfunction "TX2+_B2") (pintype "passive"))
    )
    (net (code "91") (name "unconnected-(J2-TX2--PadB3)") (class "Default")
      (node (ref "J2") (pin "B3") (pinfunction "TX2-_B3") (pintype "passive"))
    )
    (net (code "92") (name "unconnected-(U1-AREF-Pad42)") (class "Default")
      (node (ref "U1") (pin "42") (pinfunction "AREF_42") (pintype "bidirectional"))
    )
    (net (code "93") (name "unconnected-(U1-PB0(SS{slash}PCINT0)-Pad8)") (class "Default")
      (node (ref "U1") (pin "8") (pinfunction "PB0(SS/PCINT0)_8") (pintype "bidirectional"))
    )
    (net (code "94") (name "unconnected-(U1-PB4(PCINT4{slash}ADC11)-Pad28)") (class "Default")
      (node (ref "U1") (pin "28") (pinfunction "PB4(PCINT4/ADC11)_28") (pintype "bidirectional"))
    )
    (net (code "95") (name "unconnected-(U1-PB5(PCINT5{slash}OC1A{slash}ADC12{slash}~{OC4B})-Pad29)") (class "Default")
      (node (ref "U1") (pin "29") (pinfunction "PB5(PCINT5/OC1A/ADC12/~{OC4B})_29") (pintype "bidirectional"))
    )
    (net (code "96") (name "unconnected-(U1-PB6(PCINT6{slash}OC1B{slash}OC4B{slash}ADC13)-Pad30)") (class "Default")
      (node (ref "U1") (pin "30") (pinfunction "PB6(PCINT6/OC1B/OC4B/ADC13)_30") (pintype "bidirectional"))
    )
    (net (code "97") (name "unconnected-(U1-PB7(PCINT7{slash}OC0A{slash}OC1C{slash}~{RTS})-Pad12)") (class "Default")
      (node (ref "U1") (pin "12") (pinfunction "PB7(PCINT7/OC0A/OC1C/~{RTS})_12") (pintype "bidirectional"))
    )
    (net (code "98") (name "unconnected-(U1-PE6(INT.6{slash}AIN0)-Pad1)") (class "Default")
      (node (ref "U1") (pin "1") (pinfunction "PE6(INT.6/AIN0)_1") (pintype "bidirectional"))
    )
  )
)
